# ir_board.net
KiCad netlist of a schematic drawn in EAGLE
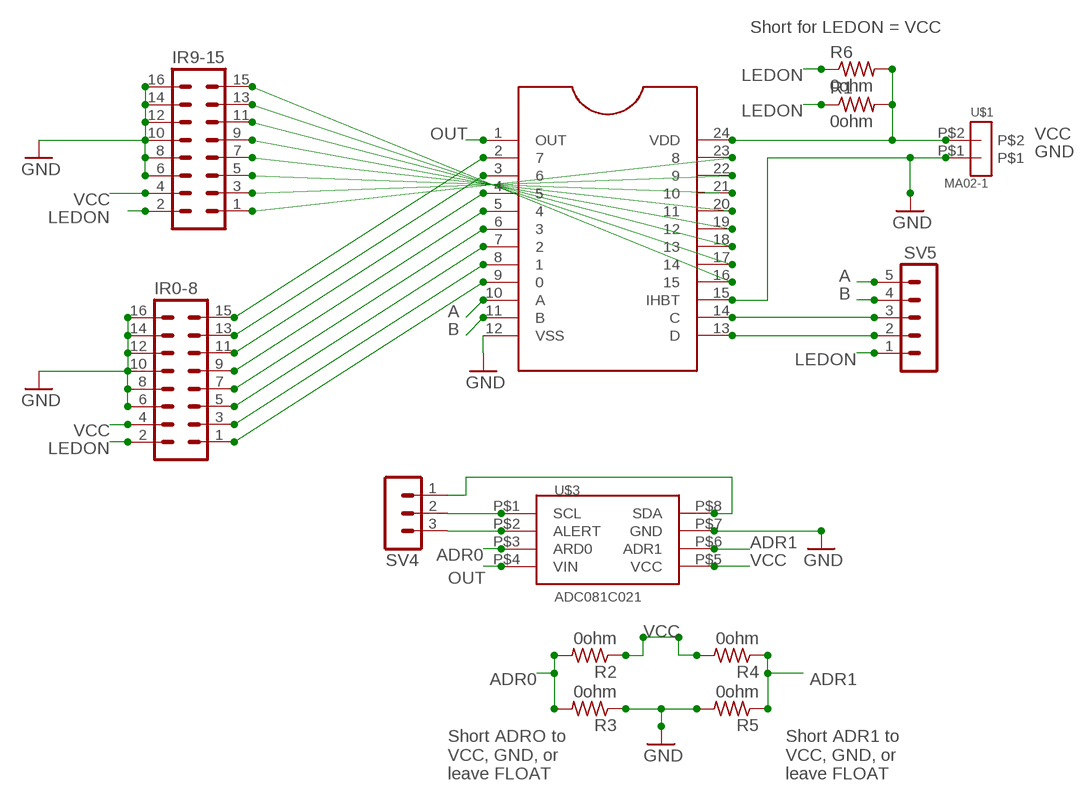
[diagram p0: schematic, sheet 1]

(export (version "E")
  (design (tool "Eeschema 10.0.6"))
  (components
    (comp (ref "IR0-8")
      (value "MA08-2")
      (footprint "eagle-import:MA08-2")
      (libsource (lib "eagle-import") (part "MA08-2"))
    )
    (comp (ref "IR9-15")
      (value "MA08-2")
      (footprint "eagle-import:MA08-2")
      (libsource (lib "eagle-import") (part "MA08-2"))
    )
    (comp (ref "R1")
      (value "0ohm")
      (footprint "eagle-import:R0805")
      (libsource (lib "eagle-import") (part "R-US_R0805"))
    )
    (comp (ref "R2")
      (value "0ohm")
      (footprint "eagle-import:R0805")
      (libsource (lib "eagle-import") (part "R-US_R0805"))
    )
    (comp (ref "R3")
      (value "0ohm")
      (footprint "eagle-import:R0805")
      (libsource (lib "eagle-import") (part "R-US_R0805"))
    )
    (comp (ref "R4")
      (value "0ohm")
      (footprint "eagle-import:R0805")
      (libsource (lib "eagle-import") (part "R-US_R0805"))
    )
    (comp (ref "R5")
      (value "0ohm")
      (footprint "eagle-import:R0805")
      (libsource (lib "eagle-import") (part "R-US_R0805"))
    )
    (comp (ref "R6")
      (value "0ohm")
      (footprint "eagle-import:R0805")
      (libsource (lib "eagle-import") (part "R-US_R0805"))
    )
    (comp (ref "SV4")
      (value "MA03-1")
      (footprint "eagle-import:MA03-1")
      (libsource (lib "eagle-import") (part "MA03-1"))
    )
    (comp (ref "SV5")
      (value "MA05-1")
      (footprint "eagle-import:MA05-1")
      (libsource (lib "eagle-import") (part "MA05-1"))
    )
    (comp (ref "U$1")
      (value "MA02-1")
      (footprint "eagle-import:MA02-1")
      (libsource (lib "eagle-import") (part "MA02-1"))
    )
    (comp (ref "U$2")
      (value "16BIT_ANALOG_MUX")
      (footprint "eagle-import:DIL24-6")
      (libsource (lib "eagle-import") (part "16BIT_ANALOG_MUX"))
    )
    (comp (ref "U$3")
      (value "ADC081C021")
      (footprint "eagle-import:TSSOP-8")
      (libsource (lib "eagle-import") (part "ADC081C021"))
    )
  )
  (nets
    (net (code "1") (name "/A") (class "Default")
      (node (ref "SV5") (pin "5") (pinfunction "5_5") (pintype "passive"))
      (node (ref "U$2") (pin "10") (pinfunction "A_10") (pintype "bidirectional"))
    )
    (net (code "2") (name "/ADR0") (class "Default")
      (node (ref "R2") (pin "2") (pinfunction "2_2") (pintype "passive"))
      (node (ref "R3") (pin "2") (pinfunction "2_2") (pintype "passive"))
      (node (ref "U$3") (pin "P$3") (pinfunction "ARD0_P$3") (pintype "bidirectional"))
    )
    (net (code "3") (name "/ADR1") (class "Default")
      (node (ref "R4") (pin "1") (pinfunction "1_1") (pintype "passive"))
      (node (ref "R5") (pin "1") (pinfunction "1_1") (pintype "passive"))
      (node (ref "U$3") (pin "P$6") (pinfunction "ADR1_P$6") (pintype "bidirectional"))
    )
    (net (code "4") (name "/B") (class "Default")
      (node (ref "SV5") (pin "4") (pinfunction "4_4") (pintype "passive"))
      (node (ref "U$2") (pin "11") (pinfunction "B_11") (pintype "bidirectional"))
    )
    (net (code "5") (name "/LEDON") (class "Default")
      (node (ref "IR0-8") (pin "2") (pinfunction "2_2") (pintype "passive"))
      (node (ref "IR9-15") (pin "2") (pinfunction "2_2") (pintype "passive"))
      (node (ref "R1") (pin "1") (pinfunction "1_1") (pintype "passive"))
      (node (ref "R6") (pin "1") (pinfunction "1_1") (pintype "passive"))
      (node (ref "SV5") (pin "1") (pinfunction "1_1") (pintype "passive"))
    )
    (net (code "6") (name "/OUT") (class "Default")
      (node (ref "U$2") (pin "1") (pinfunction "OUT_1") (pintype "bidirectional"))
      (node (ref "U$3") (pin "P$4") (pinfunction "VIN_P$4") (pintype "bidirectional"))
    )
    (net (code "7") (name "/VCC") (class "Default")
      (node (ref "IR0-8") (pin "4") (pinfunction "4_4") (pintype "passive"))
      (node (ref "IR9-15") (pin "4") (pinfunction "4_4") (pintype "passive"))
      (node (ref "R1") (pin "2") (pinfunction "2_2") (pintype "passive"))
      (node (ref "R2") (pin "1") (pinfunction "1_1") (pintype "passive"))
      (node (ref "R4") (pin "2") (pinfunction "2_2") (pintype "passive"))
      (node (ref "R6") (pin "2") (pinfunction "2_2") (pintype "passive"))
      (node (ref "U$1") (pin "P$2") (pinfunction "P$2_P$2") (pintype "bidirectional"))
      (node (ref "U$2") (pin "24") (pinfunction "VDD_24") (pintype "bidirectional"))
      (node (ref "U$3") (pin "P$5") (pinfunction "VCC_P$5") (pintype "bidirectional"))
    )
    (net (code "8") (name "GND") (class "Default")
      (node (ref "IR0-8") (pin "10") (pinfunction "10_10") (pintype "passive"))
      (node (ref "IR0-8") (pin "12") (pinfunction "12_12") (pintype "passive"))
      (node (ref "IR0-8") (pin "14") (pinfunction "14_14") (pintype "passive"))
      (node (ref "IR0-8") (pin "16") (pinfunction "16_16") (pintype "passive"))
      (node (ref "IR0-8") (pin "6") (pinfunction "6_6") (pintype "passive"))
      (node (ref "IR0-8") (pin "8") (pinfunction "8_8") (pintype "passive"))
      (node (ref "IR9-15") (pin "10") (pinfunction "10_10") (pintype "passive"))
      (node (ref "IR9-15") (pin "12") (pinfunction "12_12") (pintype "passive"))
      (node (ref "IR9-15") (pin "14") (pinfunction "14_14") (pintype "passive"))
      (node (ref "IR9-15") (pin "16") (pinfunction "16_16") (pintype "passive"))
      (node (ref "IR9-15") (pin "6") (pinfunction "6_6") (pintype "passive"))
      (node (ref "IR9-15") (pin "8") (pinfunction "8_8") (pintype "passive"))
      (node (ref "R3") (pin "1") (pinfunction "1_1") (pintype "passive"))
      (node (ref "R5") (pin "2") (pinfunction "2_2") (pintype "passive"))
      (node (ref "U$1") (pin "P$1") (pinfunction "P$1_P$1") (pintype "bidirectional"))
      (node (ref "U$2") (pin "12") (pinfunction "VSS_12") (pintype "bidirectional"))
      (node (ref "U$2") (pin "15") (pinfunction "IHBT_15") (pintype "bidirectional"))
      (node (ref "U$3") (pin "P$7") (pinfunction "GND_P$7") (pintype "bidirectional"))
    )
    (net (code "9") (name "Net-(U$2-0)") (class "Default")
      (node (ref "IR0-8") (pin "1") (pinfunction "1_1") (pintype "passive"))
      (node (ref "U$2") (pin "9") (pinfunction "0_9") (pintype "bidirectional"))
    )
    (net (code "10") (name "Net-(U$2-1)") (class "Default")
      (node (ref "IR0-8") (pin "3") (pinfunction "3_3") (pintype "passive"))
      (node (ref "U$2") (pin "8") (pinfunction "1_8") (pintype "bidirectional"))
    )
    (net (code "11") (name "Net-(U$2-2)") (class "Default")
      (node (ref "IR0-8") (pin "5") (pinfunction "5_5") (pintype "passive"))
      (node (ref "U$2") (pin "7") (pinfunction "2_7") (pintype "bidirectional"))
    )
    (net (code "12") (name "Net-(U$2-3)") (class "Default")
      (node (ref "IR0-8") (pin "7") (pinfunction "7_7") (pintype "passive"))
      (node (ref "U$2") (pin "6") (pinfunction "3_6") (pintype "bidirectional"))
    )
    (net (code "13") (name "Net-(U$2-4)") (class "Default")
      (node (ref "IR0-8") (pin "9") (pinfunction "9_9") (pintype "passive"))
      (node (ref "U$2") (pin "5") (pinfunction "4_5") (pintype "bidirectional"))
    )
    (net (code "14") (name "Net-(U$2-5)") (class "Default")
      (node (ref "IR0-8") (pin "11") (pinfunction "11_11") (pintype "passive"))
      (node (ref "U$2") (pin "4") (pinfunction "5_4") (pintype "bidirectional"))
    )
    (net (code "15") (name "Net-(U$2-6)") (class "Default")
      (node (ref "IR0-8") (pin "13") (pinfunction "13_13") (pintype "passive"))
      (node (ref "U$2") (pin "3") (pinfunction "6_3") (pintype "bidirectional"))
    )
    (net (code "16") (name "Net-(U$2-7)") (class "Default")
      (node (ref "IR0-8") (pin "15") (pinfunction "15_15") (pintype "passive"))
      (node (ref "U$2") (pin "2") (pinfunction "7_2") (pintype "bidirectional"))
    )
    (net (code "17") (name "Net-(U$2-8)") (class "Default")
      (node (ref "IR9-15") (pin "1") (pinfunction "1_1") (pintype "passive"))
      (node (ref "U$2") (pin "23") (pinfunction "8_23") (pintype "bidirectional"))
    )
    (net (code "18") (name "Net-(U$2-9)") (class "Default")
      (node (ref "IR9-15") (pin "3") (pinfunction "3_3") (pintype "passive"))
      (node (ref "U$2") (pin "22") (pinfunction "9_22") (pintype "bidirectional"))
    )
    (net (code "19") (name "Net-(U$2-10)") (class "Default")
      (node (ref "IR9-15") (pin "5") (pinfunction "5_5") (pintype "passive"))
      (node (ref "U$2") (pin "21") (pinfunction "10_21") (pintype "bidirectional"))
    )
    (net (code "20") (name "Net-(U$2-11)") (class "Default")
      (node (ref "IR9-15") (pin "7") (pinfunction "7_7") (pintype "passive"))
      (node (ref "U$2") (pin "20") (pinfunction "11_20") (pintype "bidirectional"))
    )
    (net (code "21") (name "Net-(U$2-12)") (class "Default")
      (node (ref "IR9-15") (pin "9") (pinfunction "9_9") (pintype "passive"))
      (node (ref "U$2") (pin "19") (pinfunction "12_19") (pintype "bidirectional"))
    )
    (net (code "22") (name "Net-(U$2-13)") (class "Default")
      (node (ref "IR9-15") (pin "11") (pinfunction "11_11") (pintype "passive"))
      (node (ref "U$2") (pin "18") (pinfunction "13_18") (pintype "bidirectional"))
    )
    (net (code "23") (name "Net-(U$2-14)") (class "Default")
      (node (ref "IR9-15") (pin "13") (pinfunction "13_13") (pintype "passive"))
      (node (ref "U$2") (pin "17") (pinfunction "14_17") (pintype "bidirectional"))
    )
    (net (code "24") (name "Net-(U$2-15)") (class "Default")
      (node (ref "IR9-15") (pin "15") (pinfunction "15_15") (pintype "passive"))
      (node (ref "U$2") (pin "16") (pinfunction "15_16") (pintype "bidirectional"))
    )
    (net (code "25") (name "Net-(U$2-C)") (class "Default")
      (node (ref "SV5") (pin "3") (pinfunction "3_3") (pintype "passive"))
      (node (ref "U$2") (pin "14") (pinfunction "C_14") (pintype "bidirectional"))
    )
    (net (code "26") (name "Net-(U$2-D)") (class "Default")
      (node (ref "SV5") (pin "2") (pinfunction "2_2") (pintype "passive"))
      (node (ref "U$2") (pin "13") (pinfunction "D_13") (pintype "bidirectional"))
    )
    (net (code "27") (name "Net-(U$3-ALERT)") (class "Default")
      (node (ref "SV4") (pin "3") (pinfunction "3_3") (pintype "passive"))
      (node (ref "U$3") (pin "P$2") (pinfunction "ALERT_P$2") (pintype "bidirectional"))
    )
    (net (code "28") (name "Net-(U$3-SCL)") (class "Default")
      (node (ref "SV4") (pin "2") (pinfunction "2_2") (pintype "passive"))
      (node (ref "U$3") (pin "P$1") (pinfunction "SCL_P$1") (pintype "bidirectional"))
    )
    (net (code "29") (name "Net-(U$3-SDA)") (class "Default")
      (node (ref "SV4") (pin "1") (pinfunction "1_1") (pintype "passive"))
      (node (ref "U$3") (pin "P$8") (pinfunction "SDA_P$8") (pintype "bidirectional"))
    )
  )
)
